# max4999.net
KiCad netlist of a schematic drawn in EAGLE
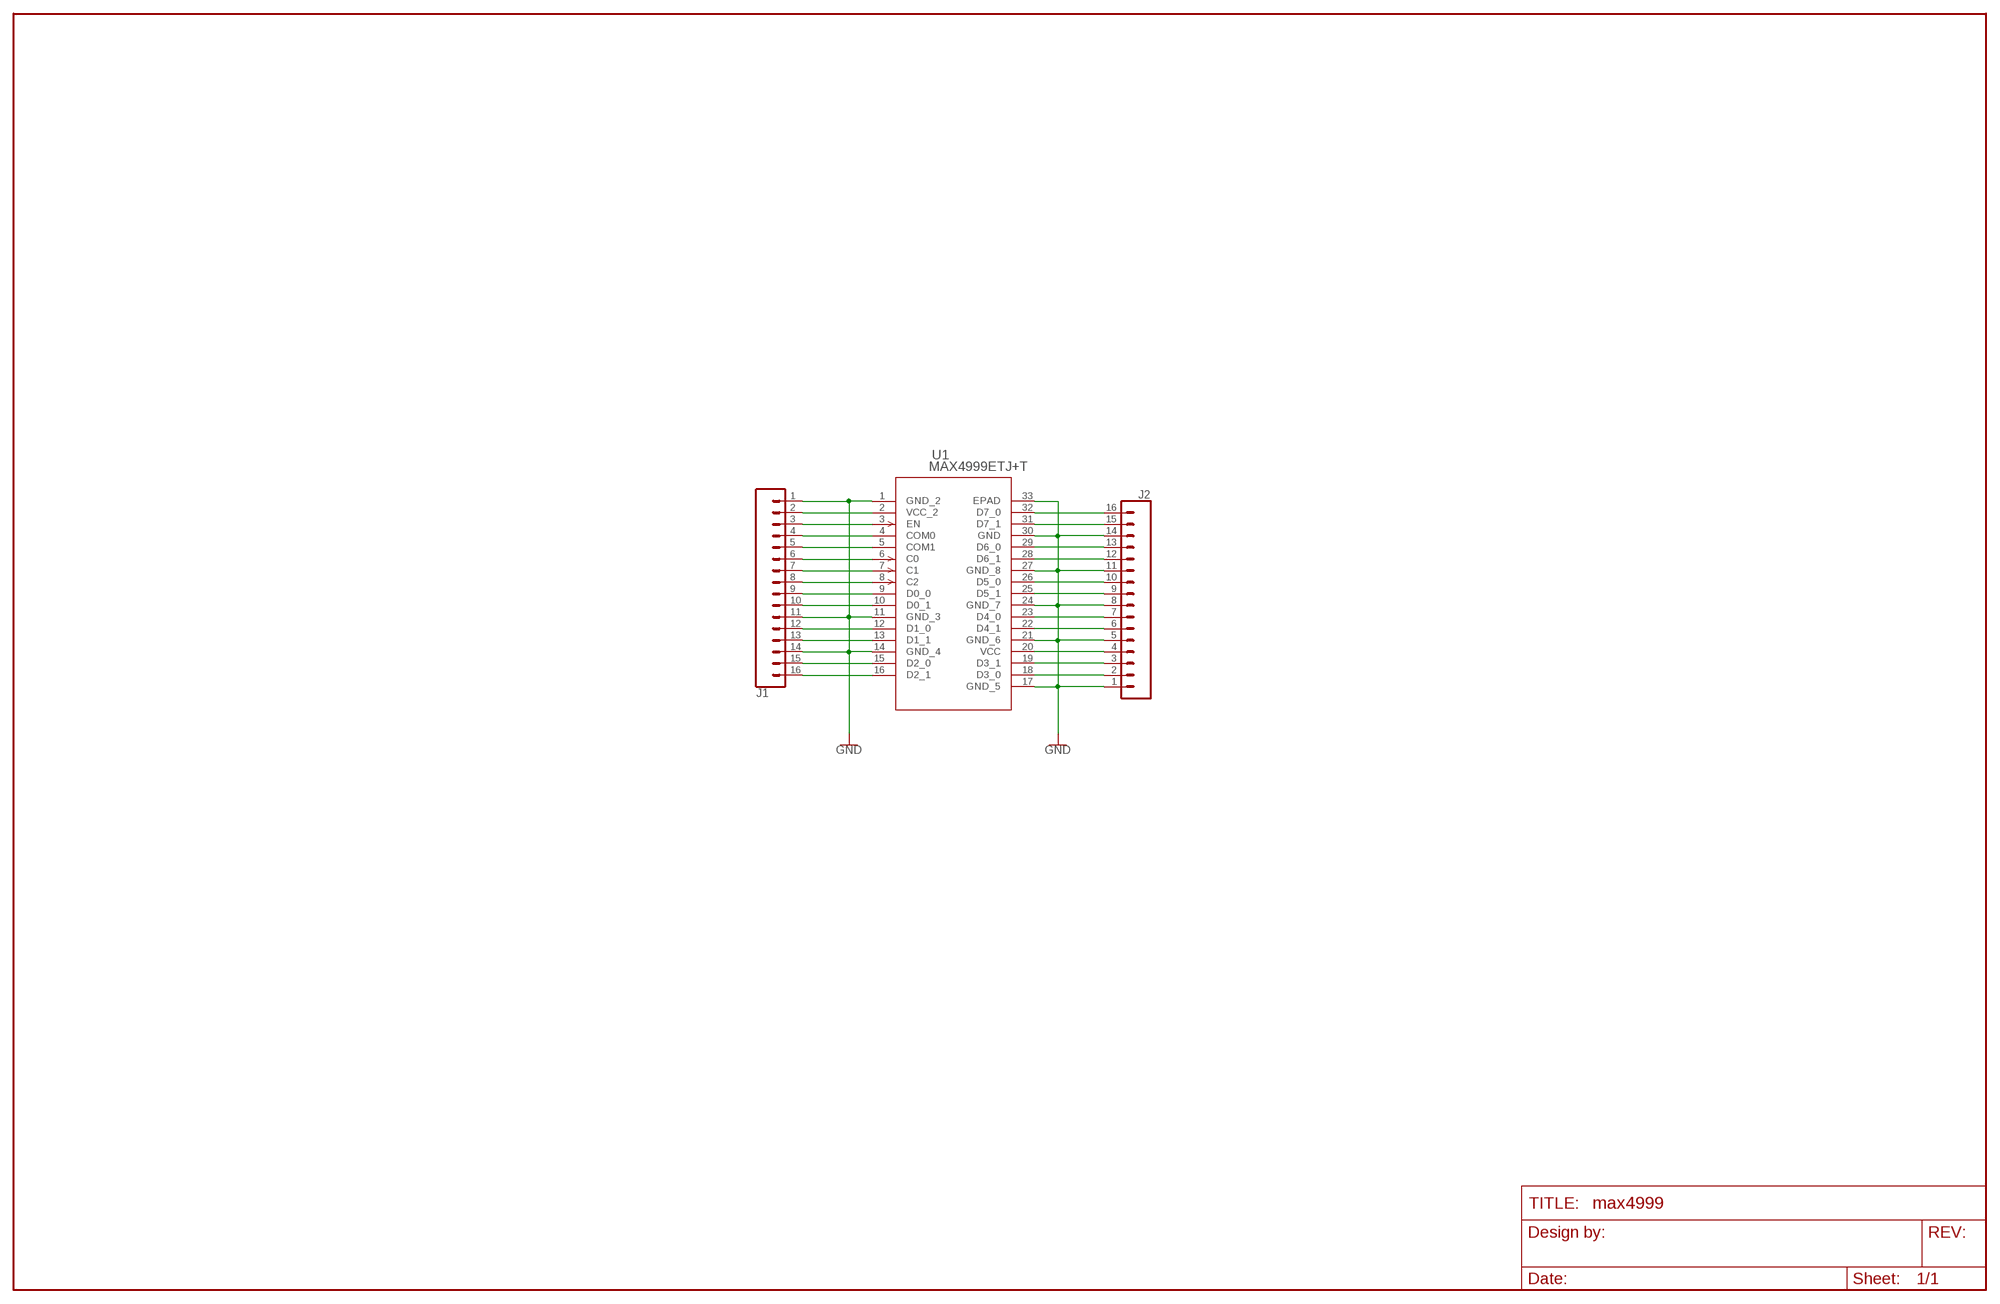
[diagram p0: schematic, sheet 1]

(export (version "E")
  (design (tool "Eeschema 10.0.6"))
  (components
    (comp (ref "FRAME1")
      (value "FRAME-LEDGERNO_FOOTPRINT")
      (footprint "eagle-import:DUMMY")
      (libsource (lib "eagle-import") (part "FRAME-LEDGERNO_FOOTPRINT"))
    )
    (comp (ref "J1")
      (value "CONN_161X16_NO_SILK")
      (footprint "eagle-import:1X16_NO_SILK")
      (libsource (lib "eagle-import") (part "CONN_161X16_NO_SILK"))
    )
    (comp (ref "J2")
      (value "CONN_161X16_NO_SILK")
      (footprint "eagle-import:1X16_NO_SILK")
      (libsource (lib "eagle-import") (part "CONN_161X16_NO_SILK"))
    )
    (comp (ref "U1")
      (value "MAX4999ETJ+T")
      (footprint "eagle-import:21-0140_T3255+4_MXM")
      (fields (field (name "COPYRIGHT") "Copyright (C) 2022 Ultra Librarian. All rights reserved."))
      (libsource (lib "eagle-import") (part "MAX4999ETJ+T"))
    )
  )
  (nets
    (net (code "1") (name "GND") (class "Default")
      (node (ref "J1") (pin "1") (pinfunction "1_1") (pintype "passive"))
      (node (ref "J1") (pin "11") (pinfunction "11_11") (pintype "passive"))
      (node (ref "J1") (pin "14") (pinfunction "14_14") (pintype "passive"))
      (node (ref "J2") (pin "1") (pinfunction "1_1") (pintype "passive"))
      (node (ref "J2") (pin "11") (pinfunction "11_11") (pintype "passive"))
      (node (ref "J2") (pin "14") (pinfunction "14_14") (pintype "passive"))
      (node (ref "J2") (pin "5") (pinfunction "5_5") (pintype "passive"))
      (node (ref "J2") (pin "8") (pinfunction "8_8") (pintype "passive"))
      (node (ref "U1") (pin "1") (pinfunction "GND_2_1") (pintype "power_in"))
      (node (ref "U1") (pin "11") (pinfunction "GND_3_11") (pintype "power_in"))
      (node (ref "U1") (pin "14") (pinfunction "GND_4_14") (pintype "power_in"))
      (node (ref "U1") (pin "17") (pinfunction "GND_5_17") (pintype "power_in"))
      (node (ref "U1") (pin "21") (pinfunction "GND_6_21") (pintype "power_in"))
      (node (ref "U1") (pin "24") (pinfunction "GND_7_24") (pintype "power_in"))
      (node (ref "U1") (pin "27") (pinfunction "GND_8_27") (pintype "power_in"))
      (node (ref "U1") (pin "30") (pinfunction "GND_30") (pintype "power_in"))
      (node (ref "U1") (pin "33") (pinfunction "EPAD_33") (pintype "passive"))
    )
    (net (code "2") (name "Net-(U1-C0)") (class "Default")
      (node (ref "J1") (pin "6") (pinfunction "6_6") (pintype "passive"))
      (node (ref "U1") (pin "6") (pinfunction "C0_6") (pintype "input"))
    )
    (net (code "3") (name "Net-(U1-C1)") (class "Default")
      (node (ref "J1") (pin "7") (pinfunction "7_7") (pintype "passive"))
      (node (ref "U1") (pin "7") (pinfunction "C1_7") (pintype "input"))
    )
    (net (code "4") (name "Net-(U1-C2)") (class "Default")
      (node (ref "J1") (pin "8") (pinfunction "8_8") (pintype "passive"))
      (node (ref "U1") (pin "8") (pinfunction "C2_8") (pintype "input"))
    )
    (net (code "5") (name "Net-(U1-COM0)") (class "Default")
      (node (ref "J1") (pin "4") (pinfunction "4_4") (pintype "passive"))
      (node (ref "U1") (pin "4") (pinfunction "COM0_4") (pintype "passive"))
    )
    (net (code "6") (name "Net-(U1-COM1)") (class "Default")
      (node (ref "J1") (pin "5") (pinfunction "5_5") (pintype "passive"))
      (node (ref "U1") (pin "5") (pinfunction "COM1_5") (pintype "passive"))
    )
    (net (code "7") (name "Net-(U1-D0_0)") (class "Default")
      (node (ref "J1") (pin "9") (pinfunction "9_9") (pintype "passive"))
      (node (ref "U1") (pin "9") (pinfunction "D0_0_9") (pintype "passive"))
    )
    (net (code "8") (name "Net-(U1-D0_1)") (class "Default")
      (node (ref "J1") (pin "10") (pinfunction "10_10") (pintype "passive"))
      (node (ref "U1") (pin "10") (pinfunction "D0_1_10") (pintype "passive"))
    )
    (net (code "9") (name "Net-(U1-D1_0)") (class "Default")
      (node (ref "J1") (pin "12") (pinfunction "12_12") (pintype "passive"))
      (node (ref "U1") (pin "12") (pinfunction "D1_0_12") (pintype "passive"))
    )
    (net (code "10") (name "Net-(U1-D1_1)") (class "Default")
      (node (ref "J1") (pin "13") (pinfunction "13_13") (pintype "passive"))
      (node (ref "U1") (pin "13") (pinfunction "D1_1_13") (pintype "passive"))
    )
    (net (code "11") (name "Net-(U1-D2_0)") (class "Default")
      (node (ref "J1") (pin "15") (pinfunction "15_15") (pintype "passive"))
      (node (ref "U1") (pin "15") (pinfunction "D2_0_15") (pintype "passive"))
    )
    (net (code "12") (name "Net-(U1-D2_1)") (class "Default")
      (node (ref "J1") (pin "16") (pinfunction "16_16") (pintype "passive"))
      (node (ref "U1") (pin "16") (pinfunction "D2_1_16") (pintype "passive"))
    )
    (net (code "13") (name "Net-(U1-D3_0)") (class "Default")
      (node (ref "J2") (pin "2") (pinfunction "2_2") (pintype "passive"))
      (node (ref "U1") (pin "18") (pinfunction "D3_0_18") (pintype "passive"))
    )
    (net (code "14") (name "Net-(U1-D3_1)") (class "Default")
      (node (ref "J2") (pin "3") (pinfunction "3_3") (pintype "passive"))
      (node (ref "U1") (pin "19") (pinfunction "D3_1_19") (pintype "passive"))
    )
    (net (code "15") (name "Net-(U1-D4_0)") (class "Default")
      (node (ref "J2") (pin "7") (pinfunction "7_7") (pintype "passive"))
      (node (ref "U1") (pin "23") (pinfunction "D4_0_23") (pintype "passive"))
    )
    (net (code "16") (name "Net-(U1-D4_1)") (class "Default")
      (node (ref "J2") (pin "6") (pinfunction "6_6") (pintype "passive"))
      (node (ref "U1") (pin "22") (pinfunction "D4_1_22") (pintype "passive"))
    )
    (net (code "17") (name "Net-(U1-D5_0)") (class "Default")
      (node (ref "J2") (pin "10") (pinfunction "10_10") (pintype "passive"))
      (node (ref "U1") (pin "26") (pinfunction "D5_0_26") (pintype "passive"))
    )
    (net (code "18") (name "Net-(U1-D5_1)") (class "Default")
      (node (ref "J2") (pin "9") (pinfunction "9_9") (pintype "passive"))
      (node (ref "U1") (pin "25") (pinfunction "D5_1_25") (pintype "passive"))
    )
    (net (code "19") (name "Net-(U1-D6_0)") (class "Default")
      (node (ref "J2") (pin "13") (pinfunction "13_13") (pintype "passive"))
      (node (ref "U1") (pin "29") (pinfunction "D6_0_29") (pintype "passive"))
    )
    (net (code "20") (name "Net-(U1-D6_1)") (class "Default")
      (node (ref "J2") (pin "12") (pinfunction "12_12") (pintype "passive"))
      (node (ref "U1") (pin "28") (pinfunction "D6_1_28") (pintype "passive"))
    )
    (net (code "21") (name "Net-(U1-D7_0)") (class "Default")
      (node (ref "J2") (pin "16") (pinfunction "16_16") (pintype "passive"))
      (node (ref "U1") (pin "32") (pinfunction "D7_0_32") (pintype "passive"))
    )
    (net (code "22") (name "Net-(U1-D7_1)") (class "Default")
      (node (ref "J2") (pin "15") (pinfunction "15_15") (pintype "passive"))
      (node (ref "U1") (pin "31") (pinfunction "D7_1_31") (pintype "passive"))
    )
    (net (code "23") (name "Net-(U1-EN)") (class "Default")
      (node (ref "J1") (pin "3") (pinfunction "3_3") (pintype "passive"))
      (node (ref "U1") (pin "3") (pinfunction "EN_3") (pintype "input"))
    )
    (net (code "24") (name "Net-(U1-VCC)") (class "Default")
      (node (ref "J2") (pin "4") (pinfunction "4_4") (pintype "passive"))
      (node (ref "U1") (pin "20") (pinfunction "VCC_20") (pintype "power_in"))
    )
    (net (code "25") (name "Net-(U1-VCC_2)") (class "Default")
      (node (ref "J1") (pin "2") (pinfunction "2_2") (pintype "passive"))
      (node (ref "U1") (pin "2") (pinfunction "VCC_2_2") (pintype "power_in"))
    )
  )
)
